# Battery_protection.net
KiCad netlist of a schematic drawn in EasyEDA
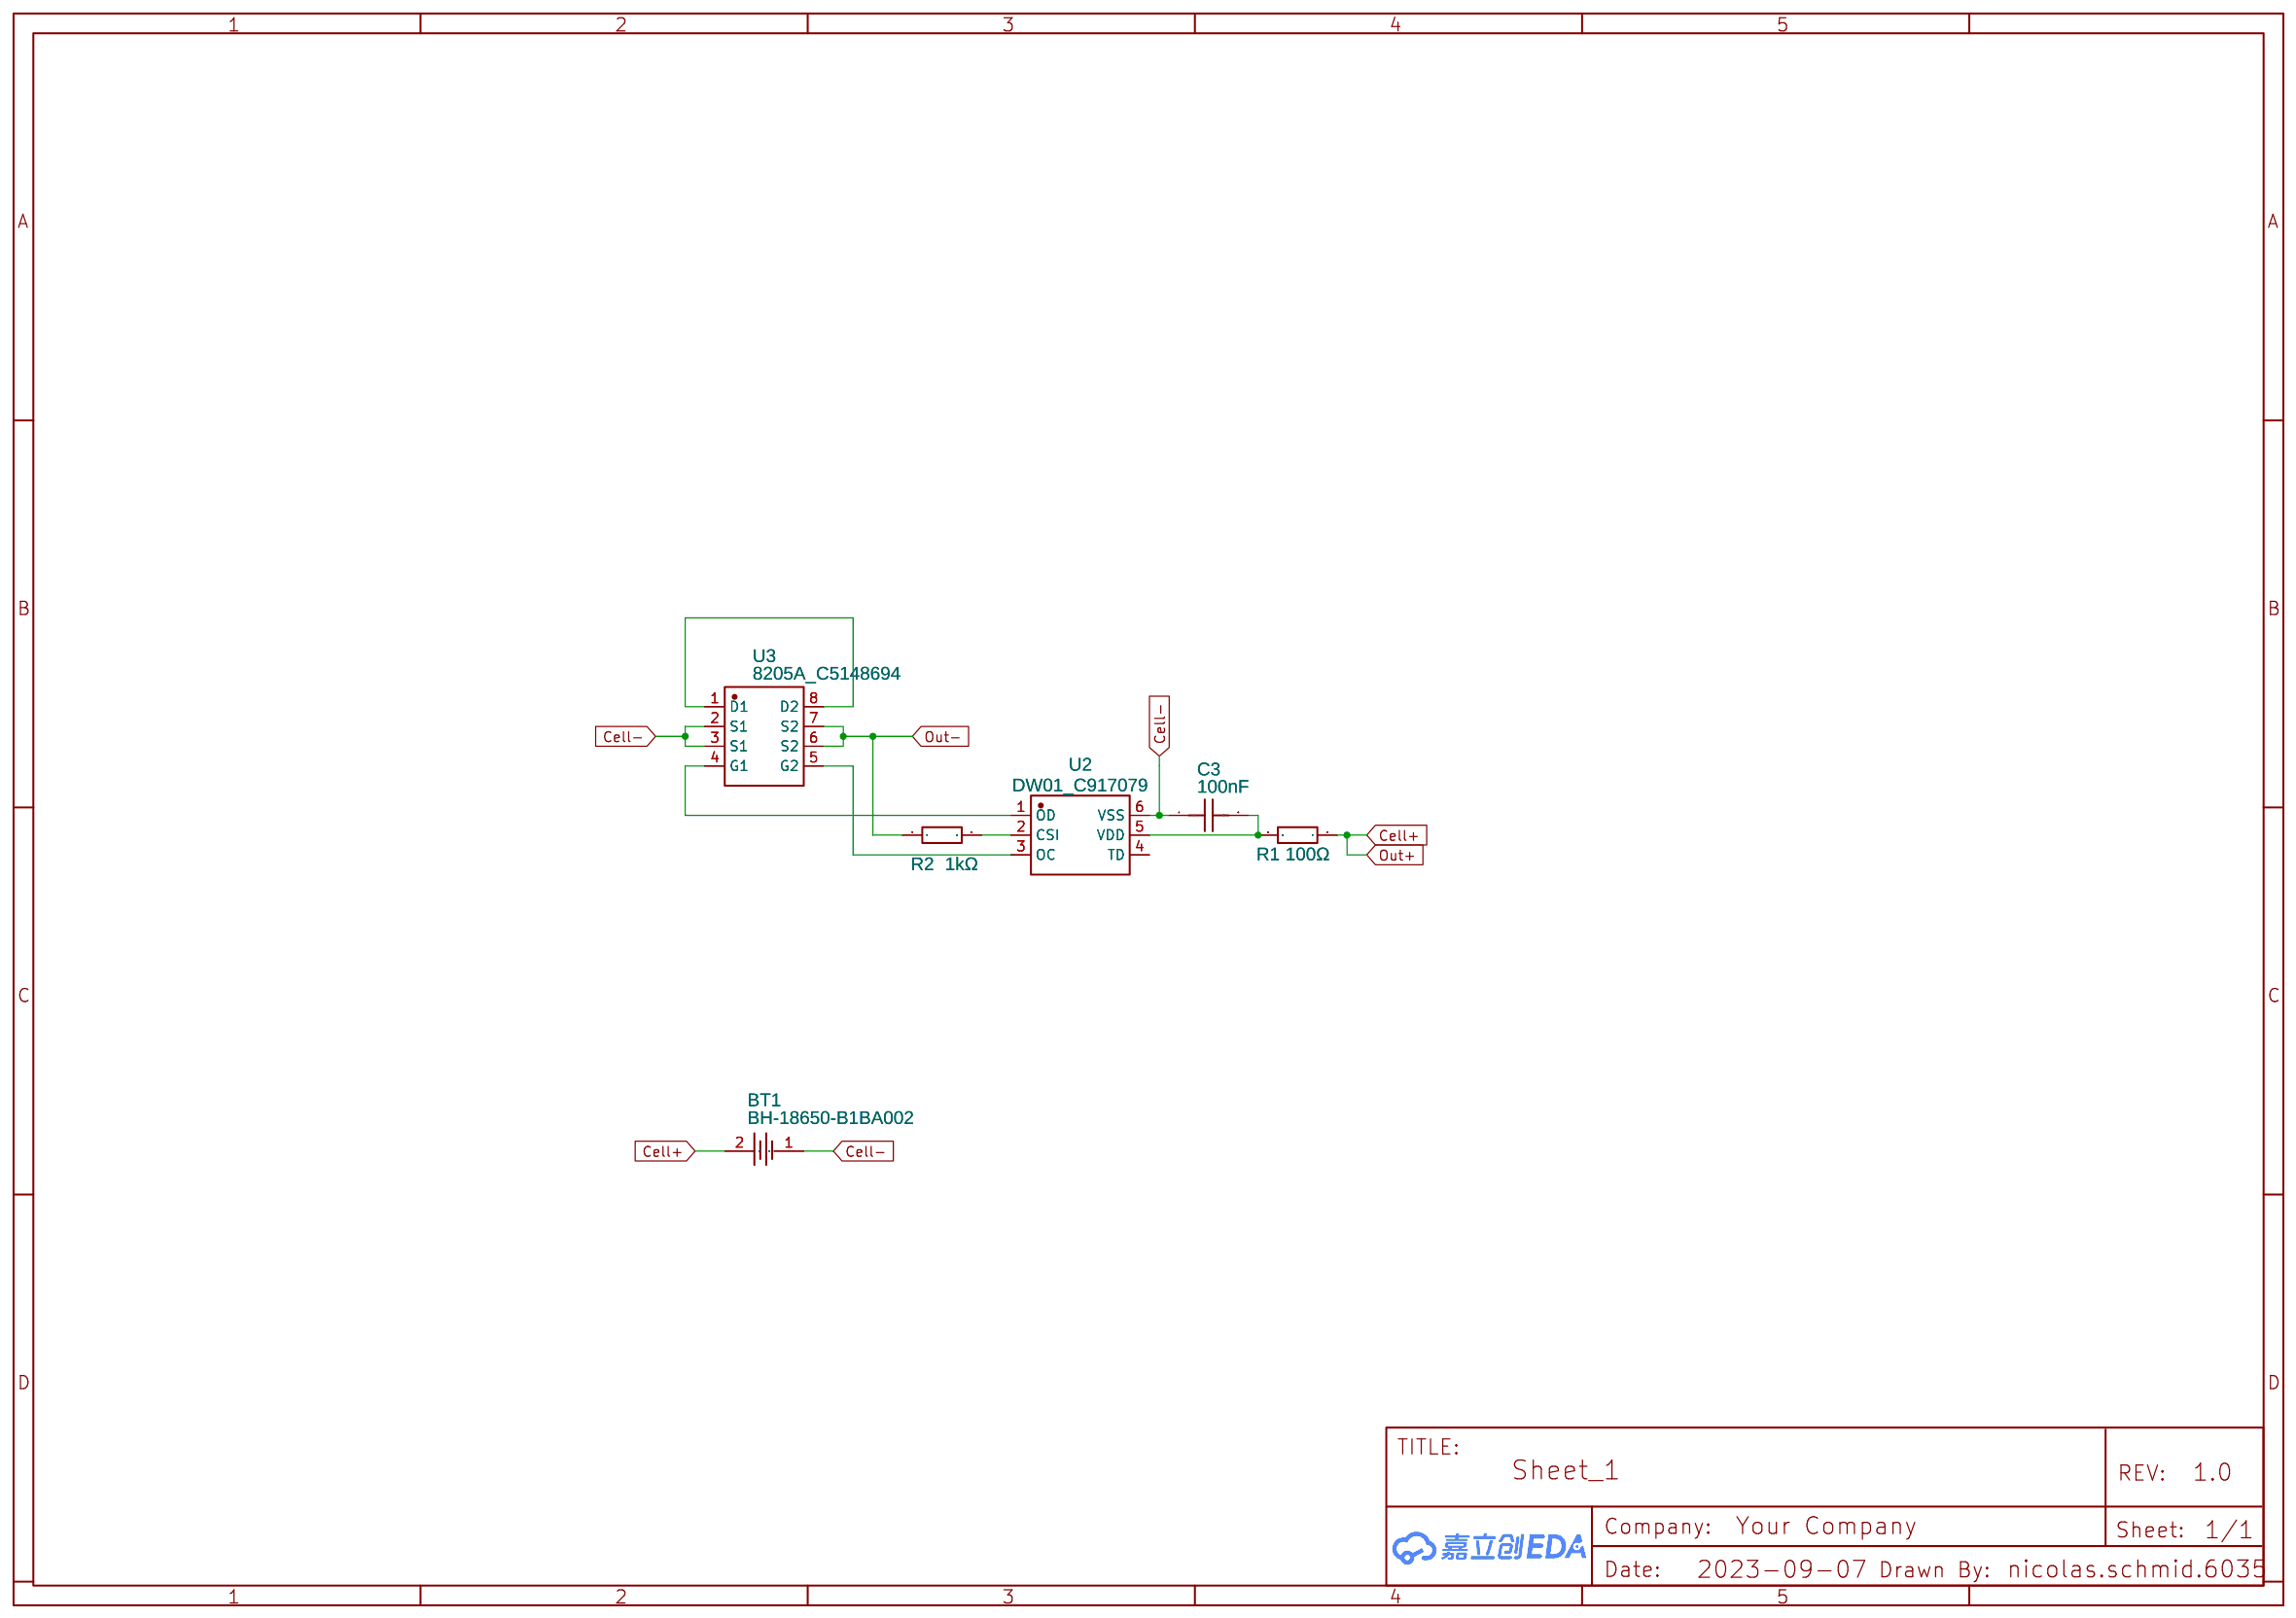
[diagram p0: schematic sheet]

(export (version "E")
  (design (tool "Eeschema 10.0.6"))
  (components
    (comp (ref "BT1")
      (value "BH-18650-B1BA002")
      (fields (field (name "Manufacturer") "MYOUNG(美阳)"))
      (libsource (lib "") (part "BH-18650-B1BA002"))
    )
    (comp (ref "C3")
      (value "100nF")
      (fields
        (field (name "Manufacturer Part") "CL05B104KB54PNC")
        (field (name "Manufacturer") "SAMSUNG(三星)")
      )
      (libsource (lib "") (part "CL05B104KB54PNC"))
    )
    (comp (ref "R1")
      (value "100Ω")
      (fields
        (field (name "Manufacturer Part") "1206W4F1000T5E")
        (field (name "Manufacturer") "UNI-ROYAL(厚声)")
      )
      (libsource (lib "") (part "1206W4F1000T5E"))
    )
    (comp (ref "R2")
      (value "1kΩ")
      (fields
        (field (name "Manufacturer Part") "1206W4F1001T5E")
        (field (name "Manufacturer") "UNI-ROYAL(厚声)")
      )
      (libsource (lib "") (part "1206W4F1001T5E"))
    )
    (comp (ref "U2")
      (value "DW01_C917079")
      (fields (field (name "Manufacturer Part") "DW01") (field (name "Manufacturer") "JSMSEMI(杰盛微)"))
      (libsource (lib "") (part "DW01_C917079"))
    )
    (comp (ref "U3")
      (value "8205A_C5148694")
      (fields (field (name "Manufacturer Part") "8205A") (field (name "Manufacturer") "HXY MOSFET(华轩阳电子)"))
      (libsource (lib "") (part "8205A_C5148694"))
    )
  )
  (nets
    (net (code "1") (name "Cell+") (class "Default")
      (node (ref "BT1") (pin "2") (pinfunction "2_2") (pintype "input"))
      (node (ref "R1") (pin "1") (pinfunction "1_1") (pintype "input"))
    )
    (net (code "2") (name "Cell-") (class "Default")
      (node (ref "BT1") (pin "1") (pinfunction "1_1") (pintype "input"))
      (node (ref "C3") (pin "1") (pinfunction "1_1") (pintype "unspecified"))
      (node (ref "U2") (pin "6") (pinfunction "VSS_6") (pintype "unspecified"))
      (node (ref "U3") (pin "2") (pinfunction "S1_2") (pintype "unspecified"))
      (node (ref "U3") (pin "3") (pinfunction "S1_3") (pintype "unspecified"))
    )
    (net (code "3") (name "Net-(U2-CSI)") (class "Default")
      (node (ref "R2") (pin "2") (pinfunction "2_2") (pintype "input"))
      (node (ref "U2") (pin "2") (pinfunction "CSI_2") (pintype "unspecified"))
    )
    (net (code "4") (name "Net-(U2-OC)") (class "Default")
      (node (ref "U2") (pin "3") (pinfunction "OC_3") (pintype "unspecified"))
      (node (ref "U3") (pin "5") (pinfunction "G2_5") (pintype "unspecified"))
    )
    (net (code "5") (name "Net-(U2-OD)") (class "Default")
      (node (ref "U2") (pin "1") (pinfunction "OD_1") (pintype "unspecified"))
      (node (ref "U3") (pin "4") (pinfunction "G1_4") (pintype "unspecified"))
    )
    (net (code "6") (name "Net-(U2-VDD)") (class "Default")
      (node (ref "C3") (pin "2") (pinfunction "2_2") (pintype "unspecified"))
      (node (ref "R1") (pin "2") (pinfunction "2_2") (pintype "input"))
      (node (ref "U2") (pin "5") (pinfunction "VDD_5") (pintype "unspecified"))
    )
    (net (code "7") (name "Net-(U3-D1)") (class "Default")
      (node (ref "U3") (pin "1") (pinfunction "D1_1") (pintype "unspecified"))
      (node (ref "U3") (pin "8") (pinfunction "D2_8") (pintype "unspecified"))
    )
    (net (code "8") (name "Out-") (class "Default")
      (node (ref "R2") (pin "1") (pinfunction "1_1") (pintype "input"))
      (node (ref "U3") (pin "6") (pinfunction "S2_6") (pintype "unspecified"))
      (node (ref "U3") (pin "7") (pinfunction "S2_7") (pintype "unspecified"))
    )
    (net (code "9") (name "unconnected-(U2-TD-Pad4)") (class "Default")
      (node (ref "U2") (pin "4") (pinfunction "TD_4") (pintype "unspecified"))
    )
  )
)
